# M62429_IIC_8.net
KiCad netlist of a schematic drawn in Altium Designer
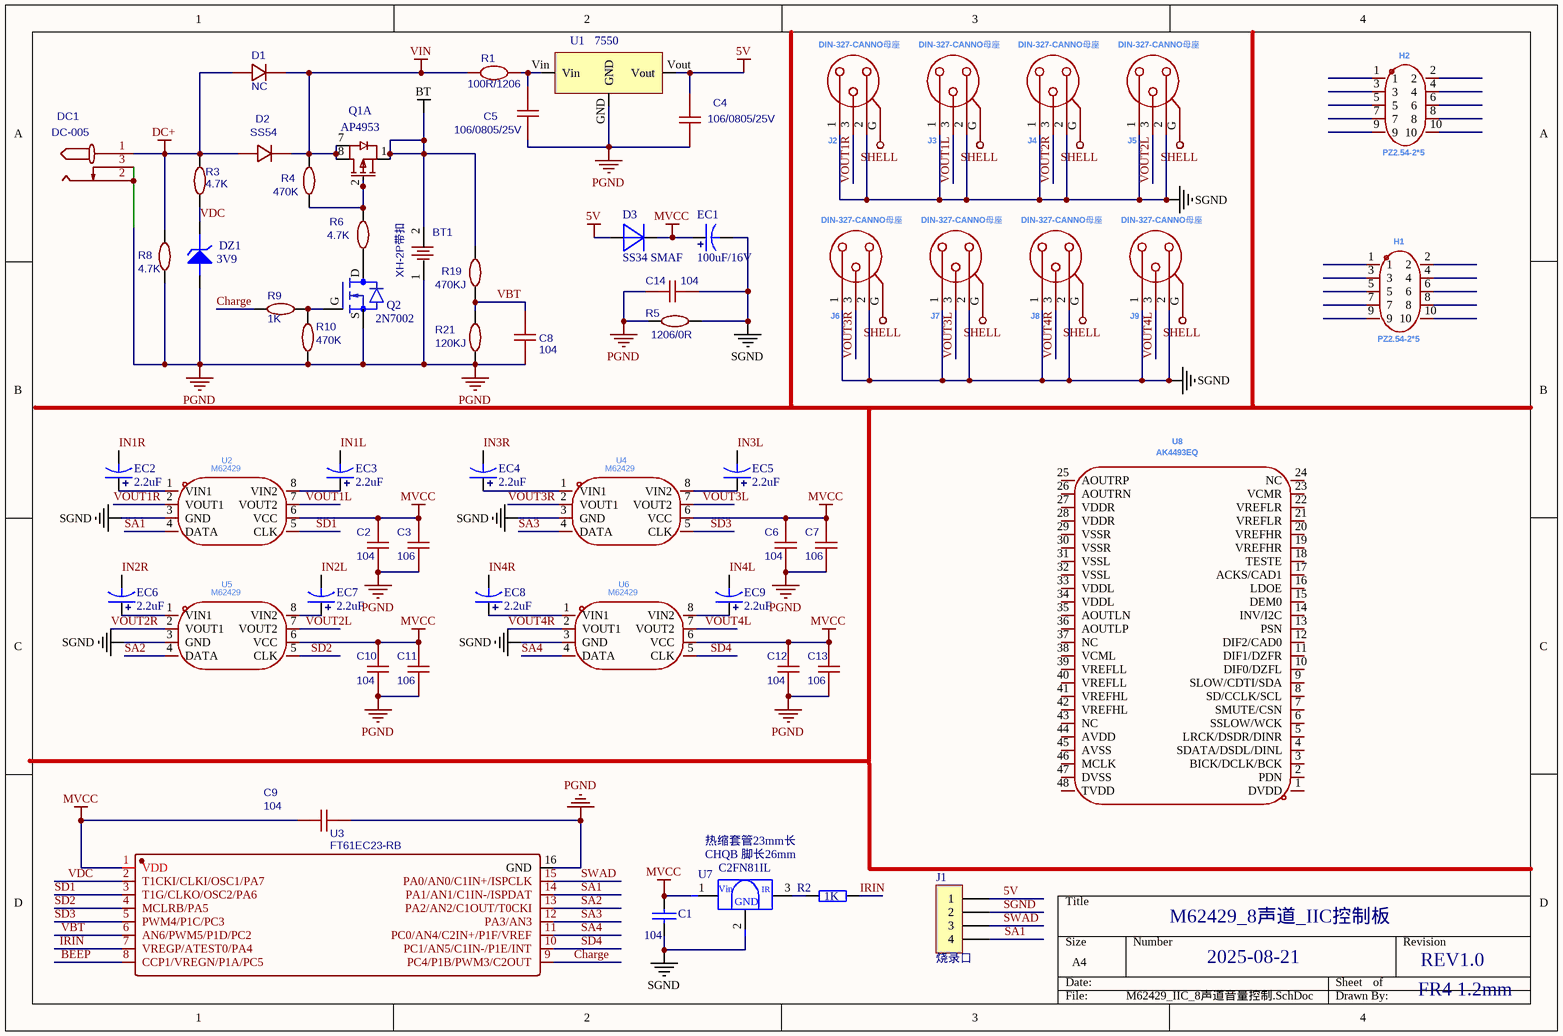
[diagram p0: M62429_IIC_8声道音量控制.SchDoc]

(export (version "E")
  (design (tool "Eeschema 10.0.6"))
  (components
    (comp (ref "BT1")
      (value "XH-2P带扣")
      (footprint "MI-VHL2-2.5")
      (fields (field (name "BOM_MANUFACTURER PART") "CR1220-2") (field (name "BOM_SUPPLIER PART") "C70381"))
      (libsource (lib "altium-import") (part "root_3_mirrored_12V_"))
    )
    (comp (ref "C1") (value "104") (footprint "0603_C") (libsource (lib "*") (part "CAP")))
    (comp (ref "C2")
      (value "104")
      (footprint "0805_c")
      (fields (field (name "CONTRIBUTOR") "LCEDA_Lib"))
      (libsource (lib "altium-import") (part "root_1_0.1u_"))
    )
    (comp (ref "C3")
      (value "106")
      (footprint "0805_c")
      (fields (field (name "CONTRIBUTOR") "LCEDA_Lib"))
      (libsource (lib "altium-import") (part "root_1_0.1u_"))
    )
    (comp (ref "C4")
      (value "106/0805/25V")
      (footprint "0805_c")
      (fields (field (name "CONTRIBUTOR") "LCEDA_Lib"))
      (libsource (lib "altium-import") (part "root_3_0.1u_"))
    )
    (comp (ref "C5")
      (value "106/0805/25V")
      (footprint "0805_c")
      (fields (field (name "CONTRIBUTOR") "LCEDA_Lib"))
      (libsource (lib "altium-import") (part "root_3_0.1u_"))
    )
    (comp (ref "C6")
      (value "104")
      (footprint "0805_c")
      (fields (field (name "CONTRIBUTOR") "LCEDA_Lib"))
      (libsource (lib "altium-import") (part "root_1_0.1u_"))
    )
    (comp (ref "C7")
      (value "106")
      (footprint "0805_c")
      (fields (field (name "CONTRIBUTOR") "LCEDA_Lib"))
      (libsource (lib "altium-import") (part "root_1_0.1u_"))
    )
    (comp (ref "C8")
      (value "104")
      (footprint "0603_C")
      (fields (field (name "CONTRIBUTOR") "LCEDA_Lib"))
      (libsource (lib "altium-import") (part "root_3_0.1u_"))
    )
    (comp (ref "C9")
      (value "104")
      (footprint "0603_C")
      (fields (field (name "CONTRIBUTOR") "LCEDA_Lib"))
      (libsource (lib "altium-import") (part "root_0_0.1u_"))
    )
    (comp (ref "C10")
      (value "104")
      (footprint "0805_c")
      (fields (field (name "CONTRIBUTOR") "LCEDA_Lib"))
      (libsource (lib "altium-import") (part "root_1_0.1u_"))
    )
    (comp (ref "C11")
      (value "106")
      (footprint "0805_c")
      (fields (field (name "CONTRIBUTOR") "LCEDA_Lib"))
      (libsource (lib "altium-import") (part "root_1_0.1u_"))
    )
    (comp (ref "C12")
      (value "104")
      (footprint "0805_c")
      (fields (field (name "CONTRIBUTOR") "LCEDA_Lib"))
      (libsource (lib "altium-import") (part "root_1_0.1u_"))
    )
    (comp (ref "C13")
      (value "106")
      (footprint "0805_c")
      (fields (field (name "CONTRIBUTOR") "LCEDA_Lib"))
      (libsource (lib "altium-import") (part "root_1_0.1u_"))
    )
    (comp (ref "C14")
      (value "104")
      (footprint "0603_C")
      (fields (field (name "CONTRIBUTOR") "LCEDA_Lib"))
      (libsource (lib "altium-import") (part "root_0_0.1u_"))
    )
    (comp (ref "D1")
      (value "NC")
      (footprint "SMA(DO-214AC)_S1")
      (fields
        (field (name "BOM_MANUFACTURER PART") "1N4007")
        (field (name "BOM_SUPPLIER PART") "C106903")
        (field (name "CONTRIBUTOR") "czy418")
      )
      (libsource (lib "altium-import") (part "root_0_SS24_"))
    )
    (comp (ref "D2")
      (value "SS54")
      (footprint "SMA(DO-214AC)_S1")
      (fields
        (field (name "BOM_MANUFACTURER PART") "1N4007")
        (field (name "BOM_SUPPLIER PART") "C106903")
        (field (name "CONTRIBUTOR") "czy418")
      )
      (libsource (lib "altium-import") (part "root_0_SS24_"))
    )
    (comp (ref "D3")
      (value "SS34 SMAF")
      (footprint "SMT-DO-214AC")
      (libsource (lib "KENNED 原理图标准封装-20160624") (part "Diode"))
    )
    (comp (ref "DC1")
      (value "DC-005")
      (footprint "DC-005")
      (fields (field (name "BOM_MANUFACTURER PART") "DC-022-A1") (field (name "BOM_SUPPLIER PART") "C92635"))
      (libsource (lib "altium-import") (part "root_0_DC-022-A1_"))
    )
    (comp (ref "DZ1")
      (value "3V9")
      (footprint "SMT-SOD123锡膏")
      (description "稳压二极管")
      (libsource (lib "二极管") (part "DIODE ZENER"))
    )
    (comp (ref "EC1")
      (value "100uF/16V")
      (footprint "DIP-EC7-2.5")
      (description "贴片电解电容")
      (libsource (lib "电容") (part "SMD_ECAP"))
    )
    (comp (ref "EC2")
      (value "2.2uF")
      (footprint "DIP-EC7-2.5")
      (description "贴片电解电容")
      (libsource (lib "电容") (part "SMD_ECAP"))
    )
    (comp (ref "EC3")
      (value "2.2uF")
      (footprint "DIP-EC7-2.5")
      (description "贴片电解电容")
      (libsource (lib "电容") (part "SMD_ECAP"))
    )
    (comp (ref "EC4")
      (value "2.2uF")
      (footprint "DIP-EC7-2.5")
      (description "贴片电解电容")
      (libsource (lib "电容") (part "SMD_ECAP"))
    )
    (comp (ref "EC5")
      (value "2.2uF")
      (footprint "DIP-EC7-2.5")
      (description "贴片电解电容")
      (libsource (lib "电容") (part "SMD_ECAP"))
    )
    (comp (ref "EC6")
      (value "2.2uF")
      (footprint "DIP-EC7-2.5")
      (description "贴片电解电容")
      (libsource (lib "电容") (part "SMD_ECAP"))
    )
    (comp (ref "EC7")
      (value "2.2uF")
      (footprint "DIP-EC7-2.5")
      (description "贴片电解电容")
      (libsource (lib "电容") (part "SMD_ECAP"))
    )
    (comp (ref "EC8")
      (value "2.2uF")
      (footprint "DIP-EC7-2.5")
      (description "贴片电解电容")
      (libsource (lib "电容") (part "SMD_ECAP"))
    )
    (comp (ref "EC9")
      (value "2.2uF")
      (footprint "DIP-EC7-2.5")
      (description "贴片电解电容")
      (libsource (lib "电容") (part "SMD_ECAP"))
    )
    (comp (ref "H1")
      (value "PZ2.54-2*5")
      (footprint "HDR-TH_10P-P2.54-V-M-R2-C5-S2.54-1")
      (fields (field (name "MANUFACTURER") "ZHOURI(洲日)"))
      (libsource (lib "altium-import") (part "root_3_PZ2.54-2*5_"))
    )
    (comp (ref "H2")
      (value "PZ2.54-2*5")
      (footprint "HDR-TH_10P-P2.54-V-M-R2-C5-S2.54-1")
      (fields (field (name "MANUFACTURER") "ZHOURI(洲日)"))
      (libsource (lib "altium-import") (part "root_3_PZ2.54-2*5_"))
    )
    (comp (ref "J1") (value "烧录口") (footprint "烧录口") (libsource (lib "XH，VH") (part "VH4")))
    (comp (ref "J2")
      (value "DIN-327-CANNO母座")
      (footprint "CONN-TH_DIN-327")
      (fields (field (name "MANUFACTURER") "HOOYA(皓宇电子)") (field (name "MANUFACTURER PART") "DIN-327"))
      (libsource (lib "altium-import") (part "root_1_DIN-327_"))
    )
    (comp (ref "J3")
      (value "DIN-327-CANNO母座")
      (footprint "CONN-TH_DIN-327")
      (fields (field (name "MANUFACTURER") "HOOYA(皓宇电子)") (field (name "MANUFACTURER PART") "DIN-327"))
      (libsource (lib "altium-import") (part "root_1_DIN-327_"))
    )
    (comp (ref "J4")
      (value "DIN-327-CANNO母座")
      (footprint "CONN-TH_DIN-327")
      (fields (field (name "MANUFACTURER") "HOOYA(皓宇电子)") (field (name "MANUFACTURER PART") "DIN-327"))
      (libsource (lib "altium-import") (part "root_1_DIN-327_"))
    )
    (comp (ref "J5")
      (value "DIN-327-CANNO母座")
      (footprint "CONN-TH_DIN-327")
      (fields (field (name "MANUFACTURER") "HOOYA(皓宇电子)") (field (name "MANUFACTURER PART") "DIN-327"))
      (libsource (lib "altium-import") (part "root_1_DIN-327_"))
    )
    (comp (ref "J6")
      (value "DIN-327-CANNO母座")
      (footprint "CONN-TH_DIN-327")
      (fields (field (name "MANUFACTURER") "HOOYA(皓宇电子)") (field (name "MANUFACTURER PART") "DIN-327"))
      (libsource (lib "altium-import") (part "root_1_DIN-327_"))
    )
    (comp (ref "J7")
      (value "DIN-327-CANNO母座")
      (footprint "CONN-TH_DIN-327")
      (fields (field (name "MANUFACTURER") "HOOYA(皓宇电子)") (field (name "MANUFACTURER PART") "DIN-327"))
      (libsource (lib "altium-import") (part "root_1_DIN-327_"))
    )
    (comp (ref "J8")
      (value "DIN-327-CANNO母座")
      (footprint "CONN-TH_DIN-327")
      (fields (field (name "MANUFACTURER") "HOOYA(皓宇电子)") (field (name "MANUFACTURER PART") "DIN-327"))
      (libsource (lib "altium-import") (part "root_1_DIN-327_"))
    )
    (comp (ref "J9")
      (value "DIN-327-CANNO母座")
      (footprint "CONN-TH_DIN-327")
      (fields (field (name "MANUFACTURER") "HOOYA(皓宇电子)") (field (name "MANUFACTURER PART") "DIN-327"))
      (libsource (lib "altium-import") (part "root_1_DIN-327_"))
    )
    (comp (ref "Q1") (value "AP4953") (libsource (lib "KENNED 原理图标准封装-2023-9-7") (part "2PMOS")))
    (comp (ref "Q2")
      (value "2N7002")
      (footprint "SMT-MOS管-SOT23锡膏")
      (libsource (lib "KENNED 原理图标准封装-2023-9-7") (part "N MOS"))
    )
    (comp (ref "R1")
      (value "100R/1206")
      (footprint "SMT-1206")
      (fields (field (name "CONTRIBUTOR") "LCEDA_Lib"))
      (libsource (lib "altium-import") (part "root_2_1k_"))
    )
    (comp (ref "R2") (value "1K") (footprint "0603_R") (libsource (lib "*") (part "RES")))
    (comp (ref "R3")
      (value "4.7K")
      (footprint "0603_R")
      (fields
        (field (name "BOM_MANUFACTURER PART") "0402WGJ0165TCE")
        (field (name "BOM_SUPPLIER PART") "C57065")
      )
      (libsource (lib "altium-import") (part "root_1_mirrored_51K_"))
    )
    (comp (ref "R4")
      (value "470K")
      (footprint "0603_R")
      (fields
        (field (name "BOM_MANUFACTURER PART") "0402WGJ0165TCE")
        (field (name "BOM_SUPPLIER PART") "C57065")
      )
      (libsource (lib "altium-import") (part "root_1_51K_"))
    )
    (comp (ref "R5")
      (value "1206/0R")
      (footprint "0603_R")
      (fields
        (field (name "BOM_MANUFACTURER PART") "0402WGJ0165TCE")
        (field (name "BOM_SUPPLIER PART") "C57065")
      )
      (libsource (lib "altium-import") (part "root_2_51K_"))
    )
    (comp (ref "R6")
      (value "4.7K")
      (footprint "0603_R")
      (fields
        (field (name "BOM_MANUFACTURER PART") "0402WGJ0165TCE")
        (field (name "BOM_SUPPLIER PART") "C57065")
      )
      (libsource (lib "altium-import") (part "root_1_51K_"))
    )
    (comp (ref "R8")
      (value "4.7K")
      (footprint "0603_R")
      (fields
        (field (name "BOM_MANUFACTURER PART") "0402WGJ0165TCE")
        (field (name "BOM_SUPPLIER PART") "C57065")
      )
      (libsource (lib "altium-import") (part "root_1_51K_"))
    )
    (comp (ref "R9")
      (value "1K")
      (footprint "0603_R")
      (fields
        (field (name "BOM_MANUFACTURER PART") "0402WGJ0165TCE")
        (field (name "BOM_SUPPLIER PART") "C57065")
      )
      (libsource (lib "altium-import") (part "root_2_51K_"))
    )
    (comp (ref "R10")
      (value "470K")
      (footprint "0603_R")
      (fields
        (field (name "BOM_MANUFACTURER PART") "0402WGJ0165TCE")
        (field (name "BOM_SUPPLIER PART") "C57065")
      )
      (libsource (lib "altium-import") (part "root_3_51K_"))
    )
    (comp (ref "R19")
      (value "470KJ")
      (footprint "0603_R")
      (fields
        (field (name "BOM_MANUFACTURER PART") "0402WGJ0165TCE")
        (field (name "BOM_SUPPLIER PART") "C57065")
      )
      (libsource (lib "altium-import") (part "root_1_51K_"))
    )
    (comp (ref "R21")
      (value "120KJ")
      (footprint "0603_R")
      (fields
        (field (name "BOM_MANUFACTURER PART") "0402WGJ0165TCE")
        (field (name "BOM_SUPPLIER PART") "C57065")
      )
      (libsource (lib "altium-import") (part "root_1_51K_"))
    )
    (comp (ref "U1")
      (value "7550")
      (footprint "SMT-LDO-SOT23锡膏")
      (libsource (lib "KENNED 原理图标准封装-20160803") (part "IC ME6208"))
    )
    (comp (ref "U2")
      (value "M62429")
      (footprint "SOIC-8_L5.0-W4.0-P1.27-LS6.0-BL")
      (fields (field (name "MANUFACTURER") "I-CORE(中微爱芯)"))
      (libsource (lib "altium-import") (part "root_0_M62429_"))
    )
    (comp (ref "U3")
      (value "FT61EC23-RB")
      (footprint "SOIC-16_150mil")
      (fields
        (field (name "BOM_SUPPLIER PART") "C2984838")
        (field (name "BOM_MANUFACTURER PART") "FT61FC23-RB")
        (field (name "CONTRIBUTOR") "lcsc")
      )
      (libsource (lib "altium-import") (part "root_0_FT61FC23-RB_"))
    )
    (comp (ref "U4")
      (value "M62429")
      (footprint "SOIC-8_L5.0-W4.0-P1.27-LS6.0-BL")
      (fields (field (name "MANUFACTURER") "I-CORE(中微爱芯)"))
      (libsource (lib "altium-import") (part "root_0_M62429_"))
    )
    (comp (ref "U5")
      (value "M62429")
      (footprint "SOIC-8_L5.0-W4.0-P1.27-LS6.0-BL")
      (fields (field (name "MANUFACTURER") "I-CORE(中微爱芯)"))
      (libsource (lib "altium-import") (part "root_0_M62429_"))
    )
    (comp (ref "U6")
      (value "M62429")
      (footprint "SOIC-8_L5.0-W4.0-P1.27-LS6.0-BL")
      (fields (field (name "MANUFACTURER") "I-CORE(中微爱芯)"))
      (libsource (lib "altium-import") (part "root_0_M62429_"))
    )
    (comp (ref "U7") (value "C2FN81IL") (footprint "MI-红外接收头卧式") (libsource (lib "黄植富") (part "红外接收头")))
    (comp (ref "U8")
      (value "AK4493EQ")
      (footprint "LQFP-48_L7.0-W7.0-P0.50-LS9.0-BL")
      (fields (field (name "MANUFACTURER") "AKM"))
      (libsource (lib "altium-import") (part "root_2_AK4493EQ_"))
    )
  )
  (nets
    (net (code "1") (name "/BEEP") (class "Default")
      (node (ref "U3") (pin "8") (pinfunction "CCP1/VREGN/P1A/PC5_8") (pintype "passive"))
    )
    (net (code "2") (name "/Charge") (class "Default")
      (node (ref "R9") (pin "2") (pinfunction "2_2") (pintype "passive"))
      (node (ref "U3") (pin "9") (pinfunction "PC4/P1B/PWM3/C2OUT_9") (pintype "passive"))
    )
    (net (code "3") (name "/IN1L") (class "Default")
      (node (ref "EC3") (pin "2") (pinfunction "2_2") (pintype "passive"))
    )
    (net (code "4") (name "/IN1R") (class "Default")
      (node (ref "EC2") (pin "2") (pinfunction "2_2") (pintype "passive"))
    )
    (net (code "5") (name "/IN2L") (class "Default")
      (node (ref "EC7") (pin "2") (pinfunction "2_2") (pintype "passive"))
    )
    (net (code "6") (name "/IN2R") (class "Default")
      (node (ref "EC6") (pin "2") (pinfunction "2_2") (pintype "passive"))
    )
    (net (code "7") (name "/IN3L") (class "Default")
      (node (ref "EC5") (pin "2") (pinfunction "2_2") (pintype "passive"))
    )
    (net (code "8") (name "/IN3R") (class "Default")
      (node (ref "EC4") (pin "2") (pinfunction "2_2") (pintype "passive"))
    )
    (net (code "9") (name "/IN4L") (class "Default")
      (node (ref "EC9") (pin "2") (pinfunction "2_2") (pintype "passive"))
    )
    (net (code "10") (name "/IN4R") (class "Default")
      (node (ref "EC8") (pin "2") (pinfunction "2_2") (pintype "passive"))
    )
    (net (code "11") (name "/IRIN") (class "Default")
      (node (ref "R2") (pin "2") (pinfunction "2_2") (pintype "passive"))
      (node (ref "U3") (pin "7") (pinfunction "VREGP/ATEST0/PA4_7") (pintype "passive"))
    )
    (net (code "12") (name "/SA1") (class "Default")
      (node (ref "J1") (pin "4") (pinfunction "4_4") (pintype "passive"))
      (node (ref "U2") (pin "4") (pinfunction "DATA_4") (pintype "passive"))
      (node (ref "U3") (pin "14") (pinfunction "PA1/AN1/C1IN-/ISPDAT_14") (pintype "passive"))
    )
    (net (code "13") (name "/SA2") (class "Default")
      (node (ref "U3") (pin "13") (pinfunction "PA2/AN2/C1OUT/T0CKI_13") (pintype "passive"))
      (node (ref "U5") (pin "4") (pinfunction "DATA_4") (pintype "passive"))
    )
    (net (code "14") (name "/SA3") (class "Default")
      (node (ref "U3") (pin "12") (pinfunction "PA3/AN3_12") (pintype "passive"))
      (node (ref "U4") (pin "4") (pinfunction "DATA_4") (pintype "passive"))
    )
    (net (code "15") (name "/SA4") (class "Default")
      (node (ref "U3") (pin "11") (pinfunction "PC0/AN4/C2IN+/P1F/VREF_11") (pintype "passive"))
      (node (ref "U6") (pin "4") (pinfunction "DATA_4") (pintype "passive"))
    )
    (net (code "16") (name "/SD1") (class "Default")
      (node (ref "U2") (pin "5") (pinfunction "CLK_5") (pintype "passive"))
      (node (ref "U3") (pin "3") (pinfunction "T1G/CLKO/OSC2/PA6_3") (pintype "passive"))
    )
    (net (code "17") (name "/SD2") (class "Default")
      (node (ref "U3") (pin "4") (pinfunction "MCLRB/PA5_4") (pintype "passive"))
      (node (ref "U5") (pin "5") (pinfunction "CLK_5") (pintype "passive"))
    )
    (net (code "18") (name "/SD3") (class "Default")
      (node (ref "U3") (pin "5") (pinfunction "PWM4/P1C/PC3_5") (pintype "passive"))
      (node (ref "U4") (pin "5") (pinfunction "CLK_5") (pintype "passive"))
    )
    (net (code "19") (name "/SD4") (class "Default")
      (node (ref "U3") (pin "10") (pinfunction "PC1/AN5/C1IN-/P1E/INT_10") (pintype "passive"))
      (node (ref "U6") (pin "5") (pinfunction "CLK_5") (pintype "passive"))
    )
    (net (code "20") (name "/SWAD") (class "Default")
      (node (ref "J1") (pin "3") (pinfunction "3_3") (pintype "passive"))
      (node (ref "U3") (pin "15") (pinfunction "PA0/AN0/C1IN+/ISPCLK_15") (pintype "passive"))
    )
    (net (code "21") (name "/VBT") (class "Default")
      (node (ref "C8") (pin "1") (pinfunction "1_1") (pintype "passive"))
      (node (ref "R19") (pin "1") (pinfunction "1_1") (pintype "passive"))
      (node (ref "R21") (pin "2") (pinfunction "2_2") (pintype "passive"))
      (node (ref "U3") (pin "6") (pinfunction "AN6/PWM5/P1D/PC2_6") (pintype "passive"))
    )
    (net (code "22") (name "/VDC") (class "Default")
      (node (ref "DZ1") (pin "2") (pinfunction "K_2") (pintype "passive"))
      (node (ref "R3") (pin "1") (pinfunction "1_1") (pintype "passive"))
      (node (ref "U3") (pin "2") (pinfunction "T1CKI/CLKI/OSC1/PA7_2") (pintype "passive"))
    )
    (net (code "23") (name "/VOUT1L") (class "Default")
      (node (ref "J3") (pin "3") (pinfunction "3_3") (pintype "passive"))
      (node (ref "U2") (pin "7") (pinfunction "VOUT2_7") (pintype "passive"))
    )
    (net (code "24") (name "/VOUT1R") (class "Default")
      (node (ref "J2") (pin "3") (pinfunction "3_3") (pintype "passive"))
      (node (ref "U2") (pin "2") (pinfunction "VOUT1_2") (pintype "passive"))
    )
    (net (code "25") (name "/VOUT2L") (class "Default")
      (node (ref "J5") (pin "3") (pinfunction "3_3") (pintype "passive"))
      (node (ref "U5") (pin "7") (pinfunction "VOUT2_7") (pintype "passive"))
    )
    (net (code "26") (name "/VOUT2R") (class "Default")
      (node (ref "J4") (pin "3") (pinfunction "3_3") (pintype "passive"))
      (node (ref "U5") (pin "2") (pinfunction "VOUT1_2") (pintype "passive"))
    )
    (net (code "27") (name "/VOUT3L") (class "Default")
      (node (ref "J7") (pin "3") (pinfunction "3_3") (pintype "passive"))
      (node (ref "U4") (pin "7") (pinfunction "VOUT2_7") (pintype "passive"))
    )
    (net (code "28") (name "/VOUT3R") (class "Default")
      (node (ref "J6") (pin "3") (pinfunction "3_3") (pintype "passive"))
      (node (ref "U4") (pin "2") (pinfunction "VOUT1_2") (pintype "passive"))
    )
    (net (code "29") (name "/VOUT4L") (class "Default")
      (node (ref "J9") (pin "3") (pinfunction "3_3") (pintype "passive"))
      (node (ref "U6") (pin "7") (pinfunction "VOUT2_7") (pintype "passive"))
    )
    (net (code "30") (name "/VOUT4R") (class "Default")
      (node (ref "J8") (pin "3") (pinfunction "3_3") (pintype "passive"))
      (node (ref "U6") (pin "2") (pinfunction "VOUT1_2") (pintype "passive"))
    )
    (net (code "31") (name "5V") (class "Default")
      (node (ref "C4") (pin "1") (pinfunction "1_1") (pintype "passive"))
      (node (ref "D3") (pin "1") (pinfunction "1_1") (pintype "passive"))
      (node (ref "J1") (pin "1") (pinfunction "1_1") (pintype "passive"))
      (node (ref "U1") (pin "Vout") (pinfunction "Vout_Vout") (pintype "passive"))
    )
    (net (code "32") (name "BT") (class "Default")
      (node (ref "BT1") (pin "2") (pinfunction "1_2") (pintype "passive"))
      (node (ref "Q1") (pin "1") (pinfunction "S_1") (pintype "passive"))
      (node (ref "R19") (pin "2") (pinfunction "2_2") (pintype "passive"))
    )
    (net (code "33") (name "DC+") (class "Default")
      (node (ref "D1") (pin "1") (pinfunction "2_1") (pintype "passive"))
      (node (ref "D2") (pin "1") (pinfunction "2_1") (pintype "passive"))
      (node (ref "DC1") (pin "1") (pinfunction "1_1") (pintype "passive"))
      (node (ref "R3") (pin "2") (pinfunction "2_2") (pintype "passive"))
      (node (ref "R8") (pin "2") (pinfunction "2_2") (pintype "passive"))
    )
    (net (code "34") (name "MVCC") (class "Default")
      (node (ref "C1") (pin "2") (pinfunction "2_2") (pintype "passive"))
      (node (ref "C10") (pin "2") (pinfunction "2_2") (pintype "passive"))
      (node (ref "C11") (pin "2") (pinfunction "2_2") (pintype "passive"))
      (node (ref "C12") (pin "2") (pinfunction "2_2") (pintype "passive"))
      (node (ref "C13") (pin "2") (pinfunction "2_2") (pintype "passive"))
      (node (ref "C2") (pin "2") (pinfunction "2_2") (pintype "passive"))
      (node (ref "C3") (pin "2") (pinfunction "2_2") (pintype "passive"))
      (node (ref "C6") (pin "2") (pinfunction "2_2") (pintype "passive"))
      (node (ref "C7") (pin "2") (pinfunction "2_2") (pintype "passive"))
      (node (ref "C9") (pin "1") (pinfunction "1_1") (pintype "passive"))
      (node (ref "D3") (pin "2") (pinfunction "2_2") (pintype "passive"))
      (node (ref "EC1") (pin "1") (pinfunction "1_1") (pintype "passive"))
      (node (ref "U2") (pin "6") (pinfunction "VCC_6") (pintype "passive"))
      (node (ref "U3") (pin "1") (pinfunction "VDD_1") (pintype "passive"))
      (node (ref "U4") (pin "6") (pinfunction "VCC_6") (pintype "passive"))
      (node (ref "U5") (pin "6") (pinfunction "VCC_6") (pintype "passive"))
      (node (ref "U6") (pin "6") (pinfunction "VCC_6") (pintype "passive"))
      (node (ref "U7") (pin "1") (pinfunction "1_1") (pintype "passive"))
    )
    (net (code "35") (name "Net-(C5-Pad1)") (class "Default")
      (node (ref "C5") (pin "1") (pinfunction "1_1") (pintype "passive"))
      (node (ref "R1") (pin "1") (pinfunction "1_1") (pintype "passive"))
      (node (ref "U1") (pin "Vin") (pinfunction "Vin_Vin") (pintype "passive"))
    )
    (net (code "36") (name "Net-(Q1A-G)") (class "Default")
      (node (ref "Q1") (pin "2") (pinfunction "G_2") (pintype "passive"))
      (node (ref "R4") (pin "1") (pinfunction "1_1") (pintype "passive"))
      (node (ref "R6") (pin "2") (pinfunction "2_2") (pintype "passive"))
    )
    (net (code "37") (name "Net-(Q2-PadD)") (class "Default")
      (node (ref "Q2") (pin "D") (pinfunction "D_D") (pintype "passive"))
      (node (ref "R6") (pin "1") (pinfunction "1_1") (pintype "passive"))
    )
    (net (code "38") (name "Net-(Q2-PadG)") (class "Default")
      (node (ref "Q2") (pin "G") (pinfunction "G_G") (pintype "passive"))
      (node (ref "R10") (pin "1") (pinfunction "1_1") (pintype "passive"))
      (node (ref "R9") (pin "1") (pinfunction "1_1") (pintype "passive"))
    )
    (net (code "39") (name "Net-(R2-Pad1)") (class "Default")
      (node (ref "R2") (pin "1") (pinfunction "1_1") (pintype "passive"))
      (node (ref "U7") (pin "3") (pinfunction "3_3") (pintype "passive"))
    )
    (net (code "40") (name "Net-(U2-VIN1)") (class "Default")
      (node (ref "EC2") (pin "1") (pinfunction "1_1") (pintype "passive"))
      (node (ref "U2") (pin "1") (pinfunction "VIN1_1") (pintype "passive"))
    )
    (net (code "41") (name "Net-(U2-VIN2)") (class "Default")
      (node (ref "EC3") (pin "1") (pinfunction "1_1") (pintype "passive"))
      (node (ref "U2") (pin "8") (pinfunction "VIN2_8") (pintype "passive"))
    )
    (net (code "42") (name "Net-(U4-VIN1)") (class "Default")
      (node (ref "EC4") (pin "1") (pinfunction "1_1") (pintype "passive"))
      (node (ref "U4") (pin "1") (pinfunction "VIN1_1") (pintype "passive"))
    )
    (net (code "43") (name "Net-(U4-VIN2)") (class "Default")
      (node (ref "EC5") (pin "1") (pinfunction "1_1") (pintype "passive"))
      (node (ref "U4") (pin "8") (pinfunction "VIN2_8") (pintype "passive"))
    )
    (net (code "44") (name "Net-(U5-VIN1)") (class "Default")
      (node (ref "EC6") (pin "1") (pinfunction "1_1") (pintype "passive"))
      (node (ref "U5") (pin "1") (pinfunction "VIN1_1") (pintype "passive"))
    )
    (net (code "45") (name "Net-(U5-VIN2)") (class "Default")
      (node (ref "EC7") (pin "1") (pinfunction "1_1") (pintype "passive"))
      (node (ref "U5") (pin "8") (pinfunction "VIN2_8") (pintype "passive"))
    )
    (net (code "46") (name "Net-(U6-VIN1)") (class "Default")
      (node (ref "EC8") (pin "1") (pinfunction "1_1") (pintype "passive"))
      (node (ref "U6") (pin "1") (pinfunction "VIN1_1") (pintype "passive"))
    )
    (net (code "47") (name "Net-(U6-VIN2)") (class "Default")
      (node (ref "EC9") (pin "1") (pinfunction "1_1") (pintype "passive"))
      (node (ref "U6") (pin "8") (pinfunction "VIN2_8") (pintype "passive"))
    )
    (net (code "48") (name "PGND") (class "Default")
      (node (ref "BT1") (pin "1") (pinfunction "2_1") (pintype "passive"))
      (node (ref "C10") (pin "1") (pinfunction "1_1") (pintype "passive"))
      (node (ref "C11") (pin "1") (pinfunction "1_1") (pintype "passive"))
      (node (ref "C12") (pin "1") (pinfunction "1_1") (pintype "passive"))
      (node (ref "C13") (pin "1") (pinfunction "1_1") (pintype "passive"))
      (node (ref "C14") (pin "1") (pinfunction "1_1") (pintype "passive"))
      (node (ref "C2") (pin "1") (pinfunction "1_1") (pintype "passive"))
      (node (ref "C3") (pin "1") (pinfunction "1_1") (pintype "passive"))
      (node (ref "C4") (pin "2") (pinfunction "2_2") (pintype "passive"))
      (node (ref "C5") (pin "2") (pinfunction "2_2") (pintype "passive"))
      (node (ref "C6") (pin "1") (pinfunction "1_1") (pintype "passive"))
      (node (ref "C7") (pin "1") (pinfunction "1_1") (pintype "passive"))
      (node (ref "C8") (pin "2") (pinfunction "2_2") (pintype "passive"))
      (node (ref "C9") (pin "2") (pinfunction "2_2") (pintype "passive"))
      (node (ref "DC1") (pin "2") (pinfunction "2_2") (pintype "passive"))
      (node (ref "DC1") (pin "3") (pinfunction "3_3") (pintype "passive"))
      (node (ref "DZ1") (pin "1") (pinfunction "A_1") (pintype "passive"))
      (node (ref "Q2") (pin "S") (pinfunction "S_S") (pintype "passive"))
      (node (ref "R10") (pin "2") (pinfunction "2_2") (pintype "passive"))
      (node (ref "R21") (pin "1") (pinfunction "1_1") (pintype "passive"))
      (node (ref "R5") (pin "2") (pinfunction "2_2") (pintype "passive"))
      (node (ref "R8") (pin "1") (pinfunction "1_1") (pintype "passive"))
      (node (ref "U1") (pin "GND") (pinfunction "GND_GND") (pintype "passive"))
      (node (ref "U3") (pin "16") (pinfunction "GND_16") (pintype "passive"))
    )
    (net (code "49") (name "SGND") (class "Default")
      (node (ref "C1") (pin "1") (pinfunction "1_1") (pintype "passive"))
      (node (ref "C14") (pin "2") (pinfunction "2_2") (pintype "passive"))
      (node (ref "EC1") (pin "2") (pinfunction "2_2") (pintype "passive"))
      (node (ref "J1") (pin "2") (pinfunction "2_2") (pintype "passive"))
      (node (ref "J2") (pin "1") (pinfunction "1_1") (pintype "passive"))
      (node (ref "J2") (pin "2") (pinfunction "2_2") (pintype "passive"))
      (node (ref "J3") (pin "1") (pinfunction "1_1") (pintype "passive"))
      (node (ref "J3") (pin "2") (pinfunction "2_2") (pintype "passive"))
      (node (ref "J4") (pin "1") (pinfunction "1_1") (pintype "passive"))
      (node (ref "J4") (pin "2") (pinfunction "2_2") (pintype "passive"))
      (node (ref "J5") (pin "1") (pinfunction "1_1") (pintype "passive"))
      (node (ref "J5") (pin "2") (pinfunction "2_2") (pintype "passive"))
      (node (ref "J6") (pin "1") (pinfunction "1_1") (pintype "passive"))
      (node (ref "J6") (pin "2") (pinfunction "2_2") (pintype "passive"))
      (node (ref "J7") (pin "1") (pinfunction "1_1") (pintype "passive"))
      (node (ref "J7") (pin "2") (pinfunction "2_2") (pintype "passive"))
      (node (ref "J8") (pin "1") (pinfunction "1_1") (pintype "passive"))
      (node (ref "J8") (pin "2") (pinfunction "2_2") (pintype "passive"))
      (node (ref "J9") (pin "1") (pinfunction "1_1") (pintype "passive"))
      (node (ref "J9") (pin "2") (pinfunction "2_2") (pintype "passive"))
      (node (ref "R5") (pin "1") (pinfunction "1_1") (pintype "passive"))
      (node (ref "U2") (pin "3") (pinfunction "GND_3") (pintype "passive"))
      (node (ref "U4") (pin "3") (pinfunction "GND_3") (pintype "passive"))
      (node (ref "U5") (pin "3") (pinfunction "GND_3") (pintype "passive"))
      (node (ref "U6") (pin "3") (pinfunction "GND_3") (pintype "passive"))
      (node (ref "U7") (pin "2") (pinfunction "2_2") (pintype "passive"))
    )
    (net (code "50") (name "SHELL") (class "Default")
      (node (ref "J2") (pin "G") (pinfunction "G_G") (pintype "passive"))
      (node (ref "J3") (pin "G") (pinfunction "G_G") (pintype "passive"))
      (node (ref "J4") (pin "G") (pinfunction "G_G") (pintype "passive"))
      (node (ref "J5") (pin "G") (pinfunction "G_G") (pintype "passive"))
      (node (ref "J6") (pin "G") (pinfunction "G_G") (pintype "passive"))
      (node (ref "J7") (pin "G") (pinfunction "G_G") (pintype "passive"))
      (node (ref "J8") (pin "G") (pinfunction "G_G") (pintype "passive"))
      (node (ref "J9") (pin "G") (pinfunction "G_G") (pintype "passive"))
    )
    (net (code "51") (name "VIN") (class "Default")
      (node (ref "D1") (pin "2") (pinfunction "1_2") (pintype "passive"))
      (node (ref "D2") (pin "2") (pinfunction "1_2") (pintype "passive"))
      (node (ref "Q1") (pin "7") (pinfunction "D_7") (pintype "passive"))
      (node (ref "Q1") (pin "8") (pinfunction "D_8") (pintype "passive"))
      (node (ref "R1") (pin "2") (pinfunction "2_2") (pintype "passive"))
      (node (ref "R4") (pin "2") (pinfunction "2_2") (pintype "passive"))
    )
    (net (code "52") (name "unconnected-(H1-Pad1)") (class "Default")
      (node (ref "H1") (pin "1") (pinfunction "1_1") (pintype "passive"))
    )
    (net (code "53") (name "unconnected-(H1-Pad2)") (class "Default")
      (node (ref "H1") (pin "2") (pinfunction "2_2") (pintype "passive"))
    )
    (net (code "54") (name "unconnected-(H1-Pad3)") (class "Default")
      (node (ref "H1") (pin "3") (pinfunction "3_3") (pintype "passive"))
    )
    (net (code "55") (name "unconnected-(H1-Pad4)") (class "Default")
      (node (ref "H1") (pin "4") (pinfunction "4_4") (pintype "passive"))
    )
    (net (code "56") (name "unconnected-(H1-Pad5)") (class "Default")
      (node (ref "H1") (pin "5") (pinfunction "5_5") (pintype "passive"))
    )
    (net (code "57") (name "unconnected-(H1-Pad6)") (class "Default")
      (node (ref "H1") (pin "6") (pinfunction "6_6") (pintype "passive"))
    )
    (net (code "58") (name "unconnected-(H1-Pad7)") (class "Default")
      (node (ref "H1") (pin "7") (pinfunction "7_7") (pintype "passive"))
    )
    (net (code "59") (name "unconnected-(H1-Pad8)") (class "Default")
      (node (ref "H1") (pin "8") (pinfunction "8_8") (pintype "passive"))
    )
    (net (code "60") (name "unconnected-(H1-Pad9)") (class "Default")
      (node (ref "H1") (pin "9") (pinfunction "9_9") (pintype "passive"))
    )
    (net (code "61") (name "unconnected-(H1-Pad10)") (class "Default")
      (node (ref "H1") (pin "10") (pinfunction "10_10") (pintype "passive"))
    )
    (net (code "62") (name "unconnected-(H2-Pad1)") (class "Default")
      (node (ref "H2") (pin "1") (pinfunction "1_1") (pintype "passive"))
    )
    (net (code "63") (name "unconnected-(H2-Pad2)") (class "Default")
      (node (ref "H2") (pin "2") (pinfunction "2_2") (pintype "passive"))
    )
    (net (code "64") (name "unconnected-(H2-Pad3)") (class "Default")
      (node (ref "H2") (pin "3") (pinfunction "3_3") (pintype "passive"))
    )
    (net (code "65") (name "unconnected-(H2-Pad4)") (class "Default")
      (node (ref "H2") (pin "4") (pinfunction "4_4") (pintype "passive"))
    )
    (net (code "66") (name "unconnected-(H2-Pad5)") (class "Default")
      (node (ref "H2") (pin "5") (pinfunction "5_5") (pintype "passive"))
    )
    (net (code "67") (name "unconnected-(H2-Pad6)") (class "Default")
      (node (ref "H2") (pin "6") (pinfunction "6_6") (pintype "passive"))
    )
    (net (code "68") (name "unconnected-(H2-Pad7)") (class "Default")
      (node (ref "H2") (pin "7") (pinfunction "7_7") (pintype "passive"))
    )
    (net (code "69") (name "unconnected-(H2-Pad8)") (class "Default")
      (node (ref "H2") (pin "8") (pinfunction "8_8") (pintype "passive"))
    )
    (net (code "70") (name "unconnected-(H2-Pad9)") (class "Default")
      (node (ref "H2") (pin "9") (pinfunction "9_9") (pintype "passive"))
    )
    (net (code "71") (name "unconnected-(H2-Pad10)") (class "Default")
      (node (ref "H2") (pin "10") (pinfunction "10_10") (pintype "passive"))
    )
    (net (code "72") (name "unconnected-(U8-ACKS{slash}CAD1-Pad17)") (class "Default")
      (node (ref "U8") (pin "17") (pinfunction "ACKS/CAD1_17") (pintype "passive"))
    )
    (net (code "73") (name "unconnected-(U8-AOUTLN-Pad35)") (class "Default")
      (node (ref "U8") (pin "35") (pinfunction "AOUTLN_35") (pintype "passive"))
    )
    (net (code "74") (name "unconnected-(U8-AOUTLP-Pad36)") (class "Default")
      (node (ref "U8") (pin "36") (pinfunction "AOUTLP_36") (pintype "passive"))
    )
    (net (code "75") (name "unconnected-(U8-AOUTRN-Pad26)") (class "Default")
      (node (ref "U8") (pin "26") (pinfunction "AOUTRN_26") (pintype "passive"))
    )
    (net (code "76") (name "unconnected-(U8-AOUTRP-Pad25)") (class "Default")
      (node (ref "U8") (pin "25") (pinfunction "AOUTRP_25") (pintype "passive"))
    )
    (net (code "77") (name "unconnected-(U8-AVDD-Pad44)") (class "Default")
      (node (ref "U8") (pin "44") (pinfunction "AVDD_44") (pintype "passive"))
    )
    (net (code "78") (name "unconnected-(U8-AVSS-Pad45)") (class "Default")
      (node (ref "U8") (pin "45") (pinfunction "AVSS_45") (pintype "passive"))
    )
    (net (code "79") (name "unconnected-(U8-BICK{slash}DCLK{slash}BCK-Pad3)") (class "Default")
      (node (ref "U8") (pin "3") (pinfunction "BICK/DCLK/BCK_3") (pintype "passive"))
    )
    (net (code "80") (name "unconnected-(U8-DEM0-Pad15)") (class "Default")
      (node (ref "U8") (pin "15") (pinfunction "DEM0_15") (pintype "passive"))
    )
    (net (code "81") (name "unconnected-(U8-DIF0{slash}DZFL-Pad10)") (class "Default")
      (node (ref "U8") (pin "10") (pinfunction "DIF0/DZFL_10") (pintype "passive"))
    )
    (net (code "82") (name "unconnected-(U8-DIF1{slash}DZFR-Pad11)") (class "Default")
      (node (ref "U8") (pin "11") (pinfunction "DIF1/DZFR_11") (pintype "passive"))
    )
    (net (code "83") (name "unconnected-(U8-DIF2{slash}CAD0-Pad12)") (class "Default")
      (node (ref "U8") (pin "12") (pinfunction "DIF2/CAD0_12") (pintype "passive"))
    )
    (net (code "84") (name "unconnected-(U8-DVDD-Pad1)") (class "Default")
      (node (ref "U8") (pin "1") (pinfunction "DVDD_1") (pintype "passive"))
    )
    (net (code "85") (name "unconnected-(U8-DVSS-Pad47)") (class "Default")
      (node (ref "U8") (pin "47") (pinfunction "DVSS_47") (pintype "passive"))
    )
    (net (code "86") (name "unconnected-(U8-INV{slash}I2C-Pad14)") (class "Default")
      (node (ref "U8") (pin "14") (pinfunction "INV/I2C_14") (pintype "passive"))
    )
    (net (code "87") (name "unconnected-(U8-LDOE-Pad16)") (class "Default")
      (node (ref "U8") (pin "16") (pinfunction "LDOE_16") (pintype "passive"))
    )
    (net (code "88") (name "unconnected-(U8-LRCK{slash}DSDR{slash}DINR-Pad5)") (class "Default")
      (node (ref "U8") (pin "5") (pinfunction "LRCK/DSDR/DINR_5") (pintype "passive"))
    )
    (net (code "89") (name "unconnected-(U8-MCLK-Pad46)") (class "Default")
      (node (ref "U8") (pin "46") (pinfunction "MCLK_46") (pintype "passive"))
    )
    (net (code "90") (name "unconnected-(U8-NC-Pad24)") (class "Default")
      (node (ref "U8") (pin "24") (pinfunction "NC_24") (pintype "passive"))
    )
    (net (code "91") (name "unconnected-(U8-NC-Pad37)") (class "Default")
      (node (ref "U8") (pin "37") (pinfunction "NC_37") (pintype "passive"))
    )
    (net (code "92") (name "unconnected-(U8-NC-Pad43)") (class "Default")
      (node (ref "U8") (pin "43") (pinfunction "NC_43") (pintype "passive"))
    )
    (net (code "93") (name "unconnected-(U8-PDN-Pad2)") (class "Default")
      (node (ref "U8") (pin "2") (pinfunction "PDN_2") (pintype "passive"))
    )
    (net (code "94") (name "unconnected-(U8-PSN-Pad13)") (class "Default")
      (node (ref "U8") (pin "13") (pinfunction "PSN_13") (pintype "passive"))
    )
    (net (code "95") (name "unconnected-(U8-SDATA{slash}DSDL{slash}DINL-Pad4)") (class "Default")
      (node (ref "U8") (pin "4") (pinfunction "SDATA/DSDL/DINL_4") (pintype "passive"))
    )
    (net (code "96") (name "unconnected-(U8-SD{slash}CCLK{slash}SCL-Pad8)") (class "Default")
      (node (ref "U8") (pin "8") (pinfunction "SD/CCLK/SCL_8") (pintype "passive"))
    )
    (net (code "97") (name "unconnected-(U8-SLOW{slash}CDTI{slash}SDA-Pad9)") (class "Default")
      (node (ref "U8") (pin "9") (pinfunction "SLOW/CDTI/SDA_9") (pintype "passive"))
    )
    (net (code "98") (name "unconnected-(U8-SMUTE{slash}CSN-Pad7)") (class "Default")
      (node (ref "U8") (pin "7") (pinfunction "SMUTE/CSN_7") (pintype "passive"))
    )
    (net (code "99") (name "unconnected-(U8-SSLOW{slash}WCK-Pad6)") (class "Default")
      (node (ref "U8") (pin "6") (pinfunction "SSLOW/WCK_6") (pintype "passive"))
    )
    (net (code "100") (name "unconnected-(U8-TESTE-Pad18)") (class "Default")
      (node (ref "U8") (pin "18") (pinfunction "TESTE_18") (pintype "passive"))
    )
    (net (code "101") (name "unconnected-(U8-TVDD-Pad48)") (class "Default")
      (node (ref "U8") (pin "48") (pinfunction "TVDD_48") (pintype "passive"))
    )
    (net (code "102") (name "unconnected-(U8-VCML-Pad38)") (class "Default")
      (node (ref "U8") (pin "38") (pinfunction "VCML_38") (pintype "passive"))
    )
    (net (code "103") (name "unconnected-(U8-VCMR-Pad23)") (class "Default")
      (node (ref "U8") (pin "23") (pinfunction "VCMR_23") (pintype "passive"))
    )
    (net (code "104") (name "unconnected-(U8-VDDL-Pad33)") (class "Default")
      (node (ref "U8") (pin "33") (pinfunction "VDDL_33") (pintype "passive"))
    )
    (net (code "105") (name "unconnected-(U8-VDDL-Pad34)") (class "Default")
      (node (ref "U8") (pin "34") (pinfunction "VDDL_34") (pintype "passive"))
    )
    (net (code "106") (name "unconnected-(U8-VDDR-Pad27)") (class "Default")
      (node (ref "U8") (pin "27") (pinfunction "VDDR_27") (pintype "passive"))
    )
    (net (code "107") (name "unconnected-(U8-VDDR-Pad28)") (class "Default")
      (node (ref "U8") (pin "28") (pinfunction "VDDR_28") (pintype "passive"))
    )
    (net (code "108") (name "unconnected-(U8-VREFHL-Pad41)") (class "Default")
      (node (ref "U8") (pin "41") (pinfunction "VREFHL_41") (pintype "passive"))
    )
    (net (code "109") (name "unconnected-(U8-VREFHL-Pad42)") (class "Default")
      (node (ref "U8") (pin "42") (pinfunction "VREFHL_42") (pintype "passive"))
    )
    (net (code "110") (name "unconnected-(U8-VREFHR-Pad19)") (class "Default")
      (node (ref "U8") (pin "19") (pinfunction "VREFHR_19") (pintype "passive"))
    )
    (net (code "111") (name "unconnected-(U8-VREFHR-Pad20)") (class "Default")
      (node (ref "U8") (pin "20") (pinfunction "VREFHR_20") (pintype "passive"))
    )
    (net (code "112") (name "unconnected-(U8-VREFLL-Pad39)") (class "Default")
      (node (ref "U8") (pin "39") (pinfunction "VREFLL_39") (pintype "passive"))
    )
    (net (code "113") (name "unconnected-(U8-VREFLL-Pad40)") (class "Default")
      (node (ref "U8") (pin "40") (pinfunction "VREFLL_40") (pintype "passive"))
    )
    (net (code "114") (name "unconnected-(U8-VREFLR-Pad21)") (class "Default")
      (node (ref "U8") (pin "21") (pinfunction "VREFLR_21") (pintype "passive"))
    )
    (net (code "115") (name "unconnected-(U8-VREFLR-Pad22)") (class "Default")
      (node (ref "U8") (pin "22") (pinfunction "VREFLR_22") (pintype "passive"))
    )
    (net (code "116") (name "unconnected-(U8-VSSL-Pad31)") (class "Default")
      (node (ref "U8") (pin "31") (pinfunction "VSSL_31") (pintype "passive"))
    )
    (net (code "117") (name "unconnected-(U8-VSSL-Pad32)") (class "Default")
      (node (ref "U8") (pin "32") (pinfunction "VSSL_32") (pintype "passive"))
    )
    (net (code "118") (name "unconnected-(U8-VSSR-Pad29)") (class "Default")
      (node (ref "U8") (pin "29") (pinfunction "VSSR_29") (pintype "passive"))
    )
    (net (code "119") (name "unconnected-(U8-VSSR-Pad30)") (class "Default")
      (node (ref "U8") (pin "30") (pinfunction "VSSR_30") (pintype "passive"))
    )
  )
)
